# Support.net
KiCad netlist of a schematic drawn in Altium Designer
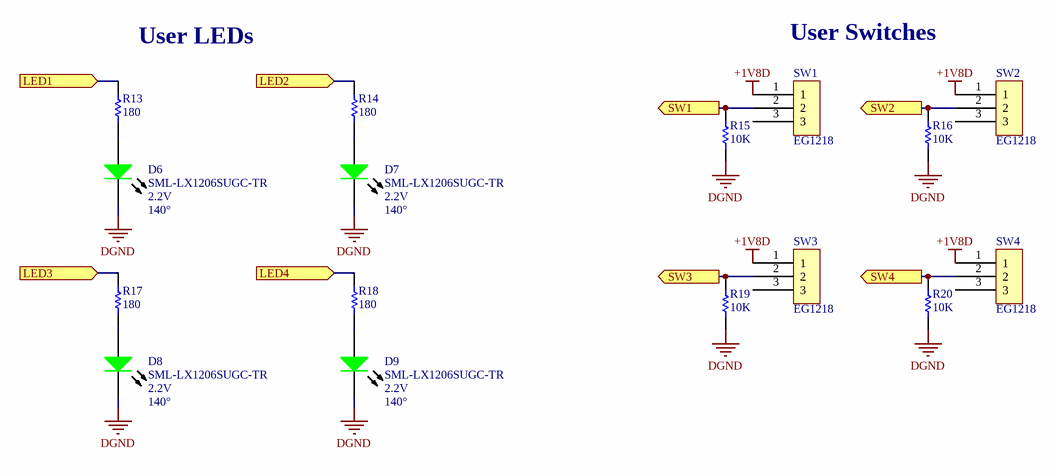
[diagram p0: Support.SchDoc]

(export (version "E")
  (design (tool "Eeschema 10.0.6"))
  (components
    (comp (ref "D6")
      (value "LED_GREEN 2")
      (footprint "DIOCP3216X11L")
      (description "LED ALINGAP ULT GRN CLR 1206 SMD")
      (fields
        (field (name "MANUFACTURER") "Lumex Opto/Components Inc")
        (field (name "MANUFACTURER PART NUMBER") "SML-LX1206SUGC-TR")
        (field (name "VOLTAGE - FORWARD (VF) TYP") "2.2V")
        (field (name "VIEWING ANGLE") "140°")
      )
      (libsource (lib "Schematic_Components") (part "LED_GREEN 2"))
    )
    (comp (ref "D7")
      (value "LED_GREEN 2")
      (footprint "DIOCP3216X11L")
      (description "LED ALINGAP ULT GRN CLR 1206 SMD")
      (fields
        (field (name "MANUFACTURER") "Lumex Opto/Components Inc")
        (field (name "MANUFACTURER PART NUMBER") "SML-LX1206SUGC-TR")
        (field (name "VOLTAGE - FORWARD (VF) TYP") "2.2V")
        (field (name "VIEWING ANGLE") "140°")
      )
      (libsource (lib "Schematic_Components") (part "LED_GREEN 2"))
    )
    (comp (ref "D8")
      (value "LED_GREEN 2")
      (footprint "DIOCP3216X11L")
      (description "LED ALINGAP ULT GRN CLR 1206 SMD")
      (fields
        (field (name "MANUFACTURER") "Lumex Opto/Components Inc")
        (field (name "MANUFACTURER PART NUMBER") "SML-LX1206SUGC-TR")
        (field (name "VOLTAGE - FORWARD (VF) TYP") "2.2V")
        (field (name "VIEWING ANGLE") "140°")
      )
      (libsource (lib "Schematic_Components") (part "LED_GREEN 2"))
    )
    (comp (ref "D9")
      (value "LED_GREEN 2")
      (footprint "DIOCP3216X11L")
      (description "LED ALINGAP ULT GRN CLR 1206 SMD")
      (fields
        (field (name "MANUFACTURER") "Lumex Opto/Components Inc")
        (field (name "MANUFACTURER PART NUMBER") "SML-LX1206SUGC-TR")
        (field (name "VOLTAGE - FORWARD (VF) TYP") "2.2V")
        (field (name "VIEWING ANGLE") "140°")
      )
      (libsource (lib "Schematic_Components") (part "LED_GREEN 2"))
    )
    (comp (ref "R13")
      (value "ERA-3AEB181V")
      (footprint "3-0603_R_L")
      (description "RES SMD 180 OHM 0.1% 1/10W 0603")
      (fields
        (field (name "MANUFACTURER") "Panasonic")
        (field (name "MANUFACTURER PART NUMBER") "ERA3AEB181V")
        (field (name "RESISTANCE") "180")
      )
      (libsource (lib "Schematic_Components_CD") (part "ERA-3AEB181V"))
    )
    (comp (ref "R14")
      (value "ERA-3AEB181V")
      (footprint "3-0603_R_L")
      (description "RES SMD 180 OHM 0.1% 1/10W 0603")
      (fields
        (field (name "MANUFACTURER") "Panasonic")
        (field (name "MANUFACTURER PART NUMBER") "ERA3AEB181V")
        (field (name "RESISTANCE") "180")
      )
      (libsource (lib "Schematic_Components_CD") (part "ERA-3AEB181V"))
    )
    (comp (ref "R15")
      (value "ERJ-3GEYJ103V")
      (footprint "3-0603_R_L")
      (description "RES 10K OHM 1/10W 5% 0603 SMD")
      (fields
        (field (name "MANUFACTURER") "Panasonic - ECG")
        (field (name "TOLERANCE") "±5%")
        (field (name "RESISTANCE (OHMS)") "10K")
      )
      (libsource (lib "Schematic_Components") (part "ERJ-3GEYJ103V"))
    )
    (comp (ref "R16")
      (value "ERJ-3GEYJ103V")
      (footprint "3-0603_R_L")
      (description "RES 10K OHM 1/10W 5% 0603 SMD")
      (fields
        (field (name "MANUFACTURER") "Panasonic - ECG")
        (field (name "TOLERANCE") "±5%")
        (field (name "RESISTANCE (OHMS)") "10K")
      )
      (libsource (lib "Schematic_Components") (part "ERJ-3GEYJ103V"))
    )
    (comp (ref "R17")
      (value "ERA-3AEB181V")
      (footprint "3-0603_R_L")
      (description "RES SMD 180 OHM 0.1% 1/10W 0603")
      (fields
        (field (name "MANUFACTURER") "Panasonic")
        (field (name "MANUFACTURER PART NUMBER") "ERA3AEB181V")
        (field (name "RESISTANCE") "180")
      )
      (libsource (lib "Schematic_Components_CD") (part "ERA-3AEB181V"))
    )
    (comp (ref "R18")
      (value "ERA-3AEB181V")
      (footprint "3-0603_R_L")
      (description "RES SMD 180 OHM 0.1% 1/10W 0603")
      (fields
        (field (name "MANUFACTURER") "Panasonic")
        (field (name "MANUFACTURER PART NUMBER") "ERA3AEB181V")
        (field (name "RESISTANCE") "180")
      )
      (libsource (lib "Schematic_Components_CD") (part "ERA-3AEB181V"))
    )
    (comp (ref "R19")
      (value "ERJ-3GEYJ103V")
      (footprint "3-0603_R_L")
      (description "RES 10K OHM 1/10W 5% 0603 SMD")
      (fields
        (field (name "MANUFACTURER") "Panasonic - ECG")
        (field (name "TOLERANCE") "±5%")
        (field (name "RESISTANCE (OHMS)") "10K")
      )
      (libsource (lib "Schematic_Components") (part "ERJ-3GEYJ103V"))
    )
    (comp (ref "R20")
      (value "ERJ-3GEYJ103V")
      (footprint "3-0603_R_L")
      (description "RES 10K OHM 1/10W 5% 0603 SMD")
      (fields
        (field (name "MANUFACTURER") "Panasonic - ECG")
        (field (name "TOLERANCE") "±5%")
        (field (name "RESISTANCE (OHMS)") "10K")
      )
      (libsource (lib "Schematic_Components") (part "ERJ-3GEYJ103V"))
    )
    (comp (ref "SW1")
      (value "Slide Switch SPDT Through Hole")
      (footprint "EG1218")
      (fields
        (field (name "MANUFACTURER") "E-Switch")
        (field (name "MANUFACTURER PART NUMBER") "EG1218")
        (field (name "PUBLISHER") "Altium Limited")
      )
      (libsource (lib "NIH_DE0_Nano_Daughter_Card_Library") (part "EG1218"))
    )
    (comp (ref "SW2")
      (value "Slide Switch SPDT Through Hole")
      (footprint "EG1218")
      (fields
        (field (name "MANUFACTURER") "E-Switch")
        (field (name "MANUFACTURER PART NUMBER") "EG1218")
        (field (name "PUBLISHER") "Altium Limited")
      )
      (libsource (lib "NIH_DE0_Nano_Daughter_Card_Library") (part "EG1218"))
    )
    (comp (ref "SW3")
      (value "Slide Switch SPDT Through Hole")
      (footprint "EG1218")
      (fields
        (field (name "MANUFACTURER") "E-Switch")
        (field (name "MANUFACTURER PART NUMBER") "EG1218")
        (field (name "PUBLISHER") "Altium Limited")
      )
      (libsource (lib "NIH_DE0_Nano_Daughter_Card_Library") (part "EG1218"))
    )
    (comp (ref "SW4")
      (value "Slide Switch SPDT Through Hole")
      (footprint "EG1218")
      (fields
        (field (name "MANUFACTURER") "E-Switch")
        (field (name "MANUFACTURER PART NUMBER") "EG1218")
        (field (name "PUBLISHER") "Altium Limited")
      )
      (libsource (lib "NIH_DE0_Nano_Daughter_Card_Library") (part "EG1218"))
    )
  )
  (nets
    (net (code "1") (name "+1V8D") (class "Default")
      (node (ref "SW1") (pin "1") (pinfunction "1_1") (pintype "passive"))
      (node (ref "SW2") (pin "1") (pinfunction "1_1") (pintype "passive"))
      (node (ref "SW3") (pin "1") (pinfunction "1_1") (pintype "passive"))
      (node (ref "SW4") (pin "1") (pinfunction "1_1") (pintype "passive"))
    )
    (net (code "2") (name "/LED1") (class "Default")
      (node (ref "R13") (pin "2") (pinfunction "2_2") (pintype "passive"))
    )
    (net (code "3") (name "/LED2") (class "Default")
      (node (ref "R14") (pin "2") (pinfunction "2_2") (pintype "passive"))
    )
    (net (code "4") (name "/LED3") (class "Default")
      (node (ref "R17") (pin "2") (pinfunction "2_2") (pintype "passive"))
    )
    (net (code "5") (name "/LED4") (class "Default")
      (node (ref "R18") (pin "2") (pinfunction "2_2") (pintype "passive"))
    )
    (net (code "6") (name "/SW1") (class "Default")
      (node (ref "R15") (pin "1") (pinfunction "1_1") (pintype "passive"))
      (node (ref "SW1") (pin "2") (pinfunction "2_2") (pintype "passive"))
    )
    (net (code "7") (name "/SW2") (class "Default")
      (node (ref "R16") (pin "1") (pinfunction "1_1") (pintype "passive"))
      (node (ref "SW2") (pin "2") (pinfunction "2_2") (pintype "passive"))
    )
    (net (code "8") (name "/SW3") (class "Default")
      (node (ref "R19") (pin "1") (pinfunction "1_1") (pintype "passive"))
      (node (ref "SW3") (pin "2") (pinfunction "2_2") (pintype "passive"))
    )
    (net (code "9") (name "/SW4") (class "Default")
      (node (ref "R20") (pin "1") (pinfunction "1_1") (pintype "passive"))
      (node (ref "SW4") (pin "2") (pinfunction "2_2") (pintype "passive"))
    )
    (net (code "10") (name "DGND") (class "Default")
      (node (ref "D6") (pin "2") (pinfunction "K_2") (pintype "passive"))
      (node (ref "D7") (pin "2") (pinfunction "K_2") (pintype "passive"))
      (node (ref "D8") (pin "2") (pinfunction "K_2") (pintype "passive"))
      (node (ref "D9") (pin "2") (pinfunction "K_2") (pintype "passive"))
      (node (ref "R15") (pin "2") (pinfunction "2_2") (pintype "passive"))
      (node (ref "R16") (pin "2") (pinfunction "2_2") (pintype "passive"))
      (node (ref "R19") (pin "2") (pinfunction "2_2") (pintype "passive"))
      (node (ref "R20") (pin "2") (pinfunction "2_2") (pintype "passive"))
    )
    (net (code "11") (name "Net-(D6-A)") (class "Default")
      (node (ref "D6") (pin "1") (pinfunction "A_1") (pintype "passive"))
      (node (ref "R13") (pin "1") (pinfunction "1_1") (pintype "passive"))
    )
    (net (code "12") (name "Net-(D7-A)") (class "Default")
      (node (ref "D7") (pin "1") (pinfunction "A_1") (pintype "passive"))
      (node (ref "R14") (pin "1") (pinfunction "1_1") (pintype "passive"))
    )
    (net (code "13") (name "Net-(D8-A)") (class "Default")
      (node (ref "D8") (pin "1") (pinfunction "A_1") (pintype "passive"))
      (node (ref "R17") (pin "1") (pinfunction "1_1") (pintype "passive"))
    )
    (net (code "14") (name "Net-(D9-A)") (class "Default")
      (node (ref "D9") (pin "1") (pinfunction "A_1") (pintype "passive"))
      (node (ref "R18") (pin "1") (pinfunction "1_1") (pintype "passive"))
    )
    (net (code "15") (name "unconnected-(SW1-Pad3)") (class "Default")
      (node (ref "SW1") (pin "3") (pinfunction "3_3") (pintype "passive"))
    )
    (net (code "16") (name "unconnected-(SW2-Pad3)") (class "Default")
      (node (ref "SW2") (pin "3") (pinfunction "3_3") (pintype "passive"))
    )
    (net (code "17") (name "unconnected-(SW3-Pad3)") (class "Default")
      (node (ref "SW3") (pin "3") (pinfunction "3_3") (pintype "passive"))
    )
    (net (code "18") (name "unconnected-(SW4-Pad3)") (class "Default")
      (node (ref "SW4") (pin "3") (pinfunction "3_3") (pintype "passive"))
    )
  )
)
